# Mux_Board.net
KiCad netlist of a schematic drawn in EAGLE
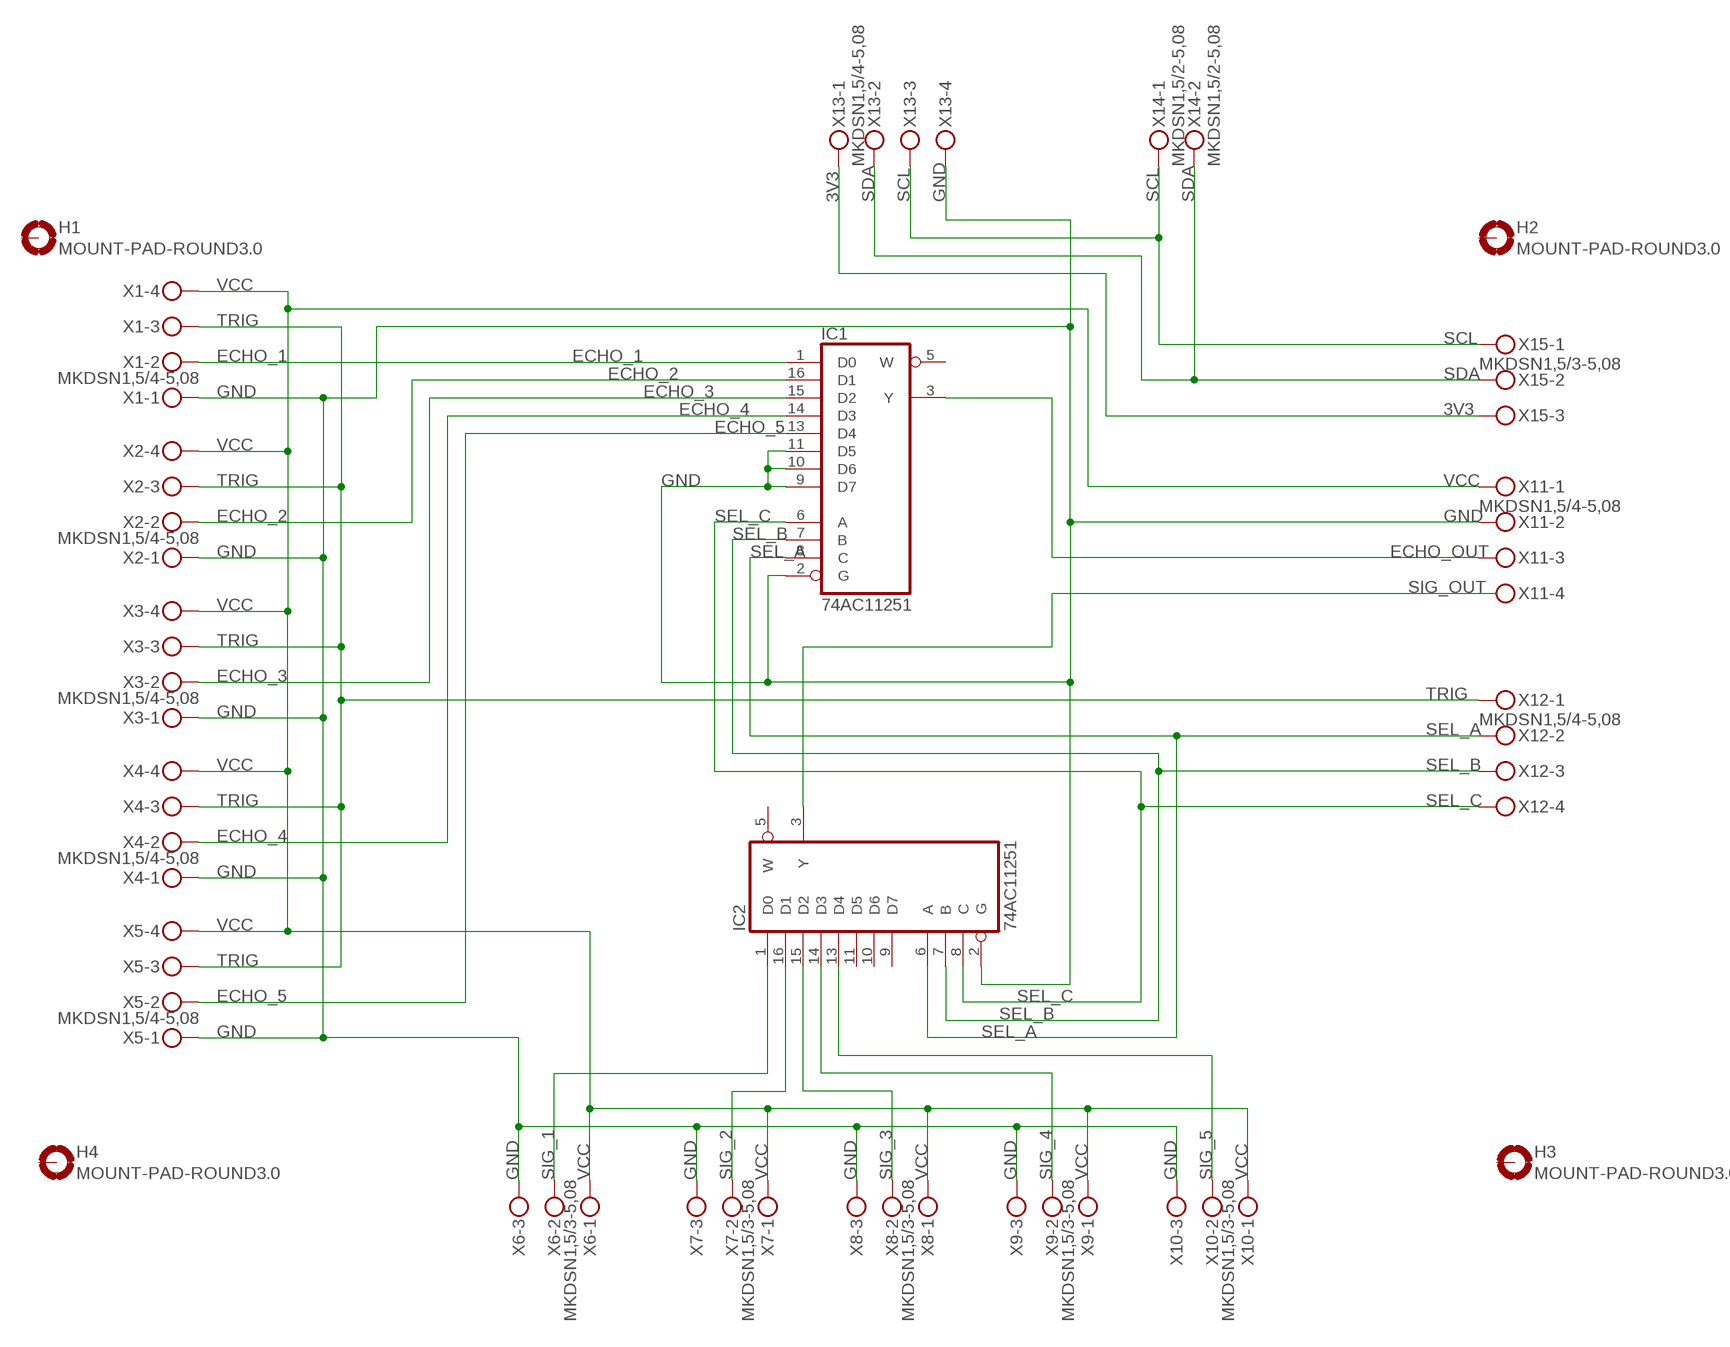
[diagram p0: schematic, sheet 1]

(export (version "E")
  (design (tool "Eeschema 10.0.6"))
  (components
    (comp (ref "H1")
      (value "MOUNT-PAD-ROUND3.0")
      (footprint "eagle-import:3,0-PAD")
      (libsource (lib "eagle-import") (part "MOUNT-PAD-ROUND3.0"))
    )
    (comp (ref "H2")
      (value "MOUNT-PAD-ROUND3.0")
      (footprint "eagle-import:3,0-PAD")
      (libsource (lib "eagle-import") (part "MOUNT-PAD-ROUND3.0"))
    )
    (comp (ref "H3")
      (value "MOUNT-PAD-ROUND3.0")
      (footprint "eagle-import:3,0-PAD")
      (libsource (lib "eagle-import") (part "MOUNT-PAD-ROUND3.0"))
    )
    (comp (ref "H4")
      (value "MOUNT-PAD-ROUND3.0")
      (footprint "eagle-import:3,0-PAD")
      (libsource (lib "eagle-import") (part "MOUNT-PAD-ROUND3.0"))
    )
    (comp (ref "IC1")
      (value "74AC11251")
      (footprint "eagle-import:DIL16")
      (libsource (lib "eagle-import") (part "74AC11251"))
    )
    (comp (ref "IC2")
      (value "74AC11251")
      (footprint "eagle-import:DIL16")
      (libsource (lib "eagle-import") (part "74AC11251"))
    )
    (comp (ref "X1")
      (value "MKDSN1,5/4-5,08")
      (footprint "eagle-import:MKDSN1,5_4-5,08")
      (libsource (lib "eagle-import") (part "MKDSN1,5/4-5,08"))
    )
    (comp (ref "X2")
      (value "MKDSN1,5/4-5,08")
      (footprint "eagle-import:MKDSN1,5_4-5,08")
      (libsource (lib "eagle-import") (part "MKDSN1,5/4-5,08"))
    )
    (comp (ref "X3")
      (value "MKDSN1,5/4-5,08")
      (footprint "eagle-import:MKDSN1,5_4-5,08")
      (libsource (lib "eagle-import") (part "MKDSN1,5/4-5,08"))
    )
    (comp (ref "X4")
      (value "MKDSN1,5/4-5,08")
      (footprint "eagle-import:MKDSN1,5_4-5,08")
      (libsource (lib "eagle-import") (part "MKDSN1,5/4-5,08"))
    )
    (comp (ref "X5")
      (value "MKDSN1,5/4-5,08")
      (footprint "eagle-import:MKDSN1,5_4-5,08")
      (libsource (lib "eagle-import") (part "MKDSN1,5/4-5,08"))
    )
    (comp (ref "X6")
      (value "MKDSN1,5/3-5,08")
      (footprint "eagle-import:MKDSN1,5_3-5,08")
      (libsource (lib "eagle-import") (part "MKDSN1,5/3-5,08"))
    )
    (comp (ref "X7")
      (value "MKDSN1,5/3-5,08")
      (footprint "eagle-import:MKDSN1,5_3-5,08")
      (libsource (lib "eagle-import") (part "MKDSN1,5/3-5,08"))
    )
    (comp (ref "X8")
      (value "MKDSN1,5/3-5,08")
      (footprint "eagle-import:MKDSN1,5_3-5,08")
      (libsource (lib "eagle-import") (part "MKDSN1,5/3-5,08"))
    )
    (comp (ref "X9")
      (value "MKDSN1,5/3-5,08")
      (footprint "eagle-import:MKDSN1,5_3-5,08")
      (libsource (lib "eagle-import") (part "MKDSN1,5/3-5,08"))
    )
    (comp (ref "X10")
      (value "MKDSN1,5/3-5,08")
      (footprint "eagle-import:MKDSN1,5_3-5,08")
      (libsource (lib "eagle-import") (part "MKDSN1,5/3-5,08"))
    )
    (comp (ref "X11")
      (value "MKDSN1,5/4-5,08")
      (footprint "eagle-import:MKDSN1,5_4-5,08")
      (libsource (lib "eagle-import") (part "MKDSN1,5/4-5,08"))
    )
    (comp (ref "X12")
      (value "MKDSN1,5/4-5,08")
      (footprint "eagle-import:MKDSN1,5_4-5,08")
      (libsource (lib "eagle-import") (part "MKDSN1,5/4-5,08"))
    )
    (comp (ref "X13")
      (value "MKDSN1,5/4-5,08")
      (footprint "eagle-import:MKDSN1,5_4-5,08")
      (libsource (lib "eagle-import") (part "MKDSN1,5/4-5,08"))
    )
    (comp (ref "X14")
      (value "MKDSN1,5/2-5,08")
      (footprint "eagle-import:MKDSN1,5_2-5,08")
      (libsource (lib "eagle-import") (part "MKDSN1,5/2-5,08"))
    )
    (comp (ref "X15")
      (value "MKDSN1,5/3-5,08")
      (footprint "eagle-import:MKDSN1,5_3-5,08")
      (libsource (lib "eagle-import") (part "MKDSN1,5/3-5,08"))
    )
  )
  (nets
    (net (code "1") (name "/3V3") (class "Default")
      (node (ref "X13") (pin "1") (pinfunction "KL_1") (pintype "passive"))
      (node (ref "X15") (pin "3") (pinfunction "KL_3") (pintype "passive"))
    )
    (net (code "2") (name "/ECHO_1") (class "Default")
      (node (ref "IC1") (pin "1") (pinfunction "D0_1") (pintype "input"))
      (node (ref "X1") (pin "2") (pinfunction "KL_2") (pintype "passive"))
    )
    (net (code "3") (name "/ECHO_2") (class "Default")
      (node (ref "IC1") (pin "16") (pinfunction "D1_16") (pintype "input"))
      (node (ref "X2") (pin "2") (pinfunction "KL_2") (pintype "passive"))
    )
    (net (code "4") (name "/ECHO_3") (class "Default")
      (node (ref "IC1") (pin "15") (pinfunction "D2_15") (pintype "input"))
      (node (ref "X3") (pin "2") (pinfunction "KL_2") (pintype "passive"))
    )
    (net (code "5") (name "/ECHO_4") (class "Default")
      (node (ref "IC1") (pin "14") (pinfunction "D3_14") (pintype "input"))
      (node (ref "X4") (pin "2") (pinfunction "KL_2") (pintype "passive"))
    )
    (net (code "6") (name "/ECHO_5") (class "Default")
      (node (ref "IC1") (pin "13") (pinfunction "D4_13") (pintype "input"))
      (node (ref "X5") (pin "2") (pinfunction "KL_2") (pintype "passive"))
    )
    (net (code "7") (name "/ECHO_OUT") (class "Default")
      (node (ref "IC1") (pin "3") (pinfunction "Y_3") (pintype "tri_state"))
      (node (ref "X11") (pin "3") (pinfunction "KL_3") (pintype "passive"))
    )
    (net (code "8") (name "/GND") (class "Default")
      (node (ref "IC1") (pin "10") (pinfunction "D6_10") (pintype "input"))
      (node (ref "IC1") (pin "11") (pinfunction "D5_11") (pintype "input"))
      (node (ref "IC1") (pin "2") (pinfunction "G_2") (pintype "input"))
      (node (ref "IC1") (pin "9") (pinfunction "D7_9") (pintype "input"))
      (node (ref "IC2") (pin "2") (pinfunction "G_2") (pintype "input"))
      (node (ref "X1") (pin "1") (pinfunction "KL_1") (pintype "passive"))
      (node (ref "X10") (pin "3") (pinfunction "KL_3") (pintype "passive"))
      (node (ref "X11") (pin "2") (pinfunction "KL_2") (pintype "passive"))
      (node (ref "X13") (pin "4") (pinfunction "KL_4") (pintype "passive"))
      (node (ref "X2") (pin "1") (pinfunction "KL_1") (pintype "passive"))
      (node (ref "X3") (pin "1") (pinfunction "KL_1") (pintype "passive"))
      (node (ref "X4") (pin "1") (pinfunction "KL_1") (pintype "passive"))
      (node (ref "X5") (pin "1") (pinfunction "KL_1") (pintype "passive"))
      (node (ref "X6") (pin "3") (pinfunction "KL_3") (pintype "passive"))
      (node (ref "X7") (pin "3") (pinfunction "KL_3") (pintype "passive"))
      (node (ref "X8") (pin "3") (pinfunction "KL_3") (pintype "passive"))
      (node (ref "X9") (pin "3") (pinfunction "KL_3") (pintype "passive"))
    )
    (net (code "9") (name "/SCL") (class "Default")
      (node (ref "X13") (pin "3") (pinfunction "KL_3") (pintype "passive"))
      (node (ref "X14") (pin "1") (pinfunction "KL_1") (pintype "passive"))
      (node (ref "X15") (pin "1") (pinfunction "KL_1") (pintype "passive"))
    )
    (net (code "10") (name "/SDA") (class "Default")
      (node (ref "X13") (pin "2") (pinfunction "KL_2") (pintype "passive"))
      (node (ref "X14") (pin "2") (pinfunction "KL_2") (pintype "passive"))
      (node (ref "X15") (pin "2") (pinfunction "KL_2") (pintype "passive"))
    )
    (net (code "11") (name "/SEL_A") (class "Default")
      (node (ref "IC1") (pin "8") (pinfunction "C_8") (pintype "input"))
      (node (ref "IC2") (pin "6") (pinfunction "A_6") (pintype "input"))
      (node (ref "X12") (pin "2") (pinfunction "KL_2") (pintype "passive"))
    )
    (net (code "12") (name "/SEL_B") (class "Default")
      (node (ref "IC1") (pin "7") (pinfunction "B_7") (pintype "input"))
      (node (ref "IC2") (pin "7") (pinfunction "B_7") (pintype "input"))
      (node (ref "X12") (pin "3") (pinfunction "KL_3") (pintype "passive"))
    )
    (net (code "13") (name "/SEL_C") (class "Default")
      (node (ref "IC1") (pin "6") (pinfunction "A_6") (pintype "input"))
      (node (ref "IC2") (pin "8") (pinfunction "C_8") (pintype "input"))
      (node (ref "X12") (pin "4") (pinfunction "KL_4") (pintype "passive"))
    )
    (net (code "14") (name "/SIG_1") (class "Default")
      (node (ref "IC2") (pin "1") (pinfunction "D0_1") (pintype "input"))
      (node (ref "X6") (pin "2") (pinfunction "KL_2") (pintype "passive"))
    )
    (net (code "15") (name "/SIG_2") (class "Default")
      (node (ref "IC2") (pin "16") (pinfunction "D1_16") (pintype "input"))
      (node (ref "X7") (pin "2") (pinfunction "KL_2") (pintype "passive"))
    )
    (net (code "16") (name "/SIG_3") (class "Default")
      (node (ref "IC2") (pin "15") (pinfunction "D2_15") (pintype "input"))
      (node (ref "X8") (pin "2") (pinfunction "KL_2") (pintype "passive"))
    )
    (net (code "17") (name "/SIG_4") (class "Default")
      (node (ref "IC2") (pin "14") (pinfunction "D3_14") (pintype "input"))
      (node (ref "X9") (pin "2") (pinfunction "KL_2") (pintype "passive"))
    )
    (net (code "18") (name "/SIG_5") (class "Default")
      (node (ref "IC2") (pin "13") (pinfunction "D4_13") (pintype "input"))
      (node (ref "X10") (pin "2") (pinfunction "KL_2") (pintype "passive"))
    )
    (net (code "19") (name "/SIG_OUT") (class "Default")
      (node (ref "IC2") (pin "3") (pinfunction "Y_3") (pintype "tri_state"))
    )
    (net (code "20") (name "/TRIG") (class "Default")
      (node (ref "X1") (pin "3") (pinfunction "KL_3") (pintype "passive"))
      (node (ref "X12") (pin "1") (pinfunction "KL_1") (pintype "passive"))
      (node (ref "X2") (pin "3") (pinfunction "KL_3") (pintype "passive"))
      (node (ref "X3") (pin "3") (pinfunction "KL_3") (pintype "passive"))
      (node (ref "X4") (pin "3") (pinfunction "KL_3") (pintype "passive"))
      (node (ref "X5") (pin "3") (pinfunction "KL_3") (pintype "passive"))
    )
    (net (code "21") (name "/VCC") (class "Default")
      (node (ref "X1") (pin "4") (pinfunction "KL_4") (pintype "passive"))
      (node (ref "X10") (pin "1") (pinfunction "KL_1") (pintype "passive"))
      (node (ref "X11") (pin "1") (pinfunction "KL_1") (pintype "passive"))
      (node (ref "X2") (pin "4") (pinfunction "KL_4") (pintype "passive"))
      (node (ref "X3") (pin "4") (pinfunction "KL_4") (pintype "passive"))
      (node (ref "X4") (pin "4") (pinfunction "KL_4") (pintype "passive"))
      (node (ref "X5") (pin "4") (pinfunction "KL_4") (pintype "passive"))
      (node (ref "X6") (pin "1") (pinfunction "KL_1") (pintype "passive"))
      (node (ref "X7") (pin "1") (pinfunction "KL_1") (pintype "passive"))
      (node (ref "X8") (pin "1") (pinfunction "KL_1") (pintype "passive"))
      (node (ref "X9") (pin "1") (pinfunction "KL_1") (pintype "passive"))
    )
    (net (code "22") (name "unconnected-(H1-MOUNT-PadB3,0)") (class "Default")
      (node (ref "H1") (pin "B3,0") (pinfunction "MOUNT_B3,0") (pintype "passive"))
    )
    (net (code "23") (name "unconnected-(H2-MOUNT-PadB3,0)") (class "Default")
      (node (ref "H2") (pin "B3,0") (pinfunction "MOUNT_B3,0") (pintype "passive"))
    )
    (net (code "24") (name "unconnected-(H3-MOUNT-PadB3,0)") (class "Default")
      (node (ref "H3") (pin "B3,0") (pinfunction "MOUNT_B3,0") (pintype "passive"))
    )
    (net (code "25") (name "unconnected-(H4-MOUNT-PadB3,0)") (class "Default")
      (node (ref "H4") (pin "B3,0") (pinfunction "MOUNT_B3,0") (pintype "passive"))
    )
    (net (code "26") (name "unconnected-(IC1A-W-Pad5)") (class "Default")
      (node (ref "IC1") (pin "5") (pinfunction "W_5") (pintype "tri_state"))
    )
    (net (code "27") (name "unconnected-(IC2A-D5-Pad11)") (class "Default")
      (node (ref "IC2") (pin "11") (pinfunction "D5_11") (pintype "input"))
    )
    (net (code "28") (name "unconnected-(IC2A-D6-Pad10)") (class "Default")
      (node (ref "IC2") (pin "10") (pinfunction "D6_10") (pintype "input"))
    )
    (net (code "29") (name "unconnected-(IC2A-D7-Pad9)") (class "Default")
      (node (ref "IC2") (pin "9") (pinfunction "D7_9") (pintype "input"))
    )
    (net (code "30") (name "unconnected-(IC2A-W-Pad5)") (class "Default")
      (node (ref "IC2") (pin "5") (pinfunction "W_5") (pintype "tri_state"))
    )
    (net (code "31") (name "unconnected-(X11D-KL-Pad4)") (class "Default")
      (node (ref "X11") (pin "4") (pinfunction "KL_4") (pintype "passive"))
    )
  )
)
